# design.net
KiCad netlist of a schematic drawn in Altium Designer
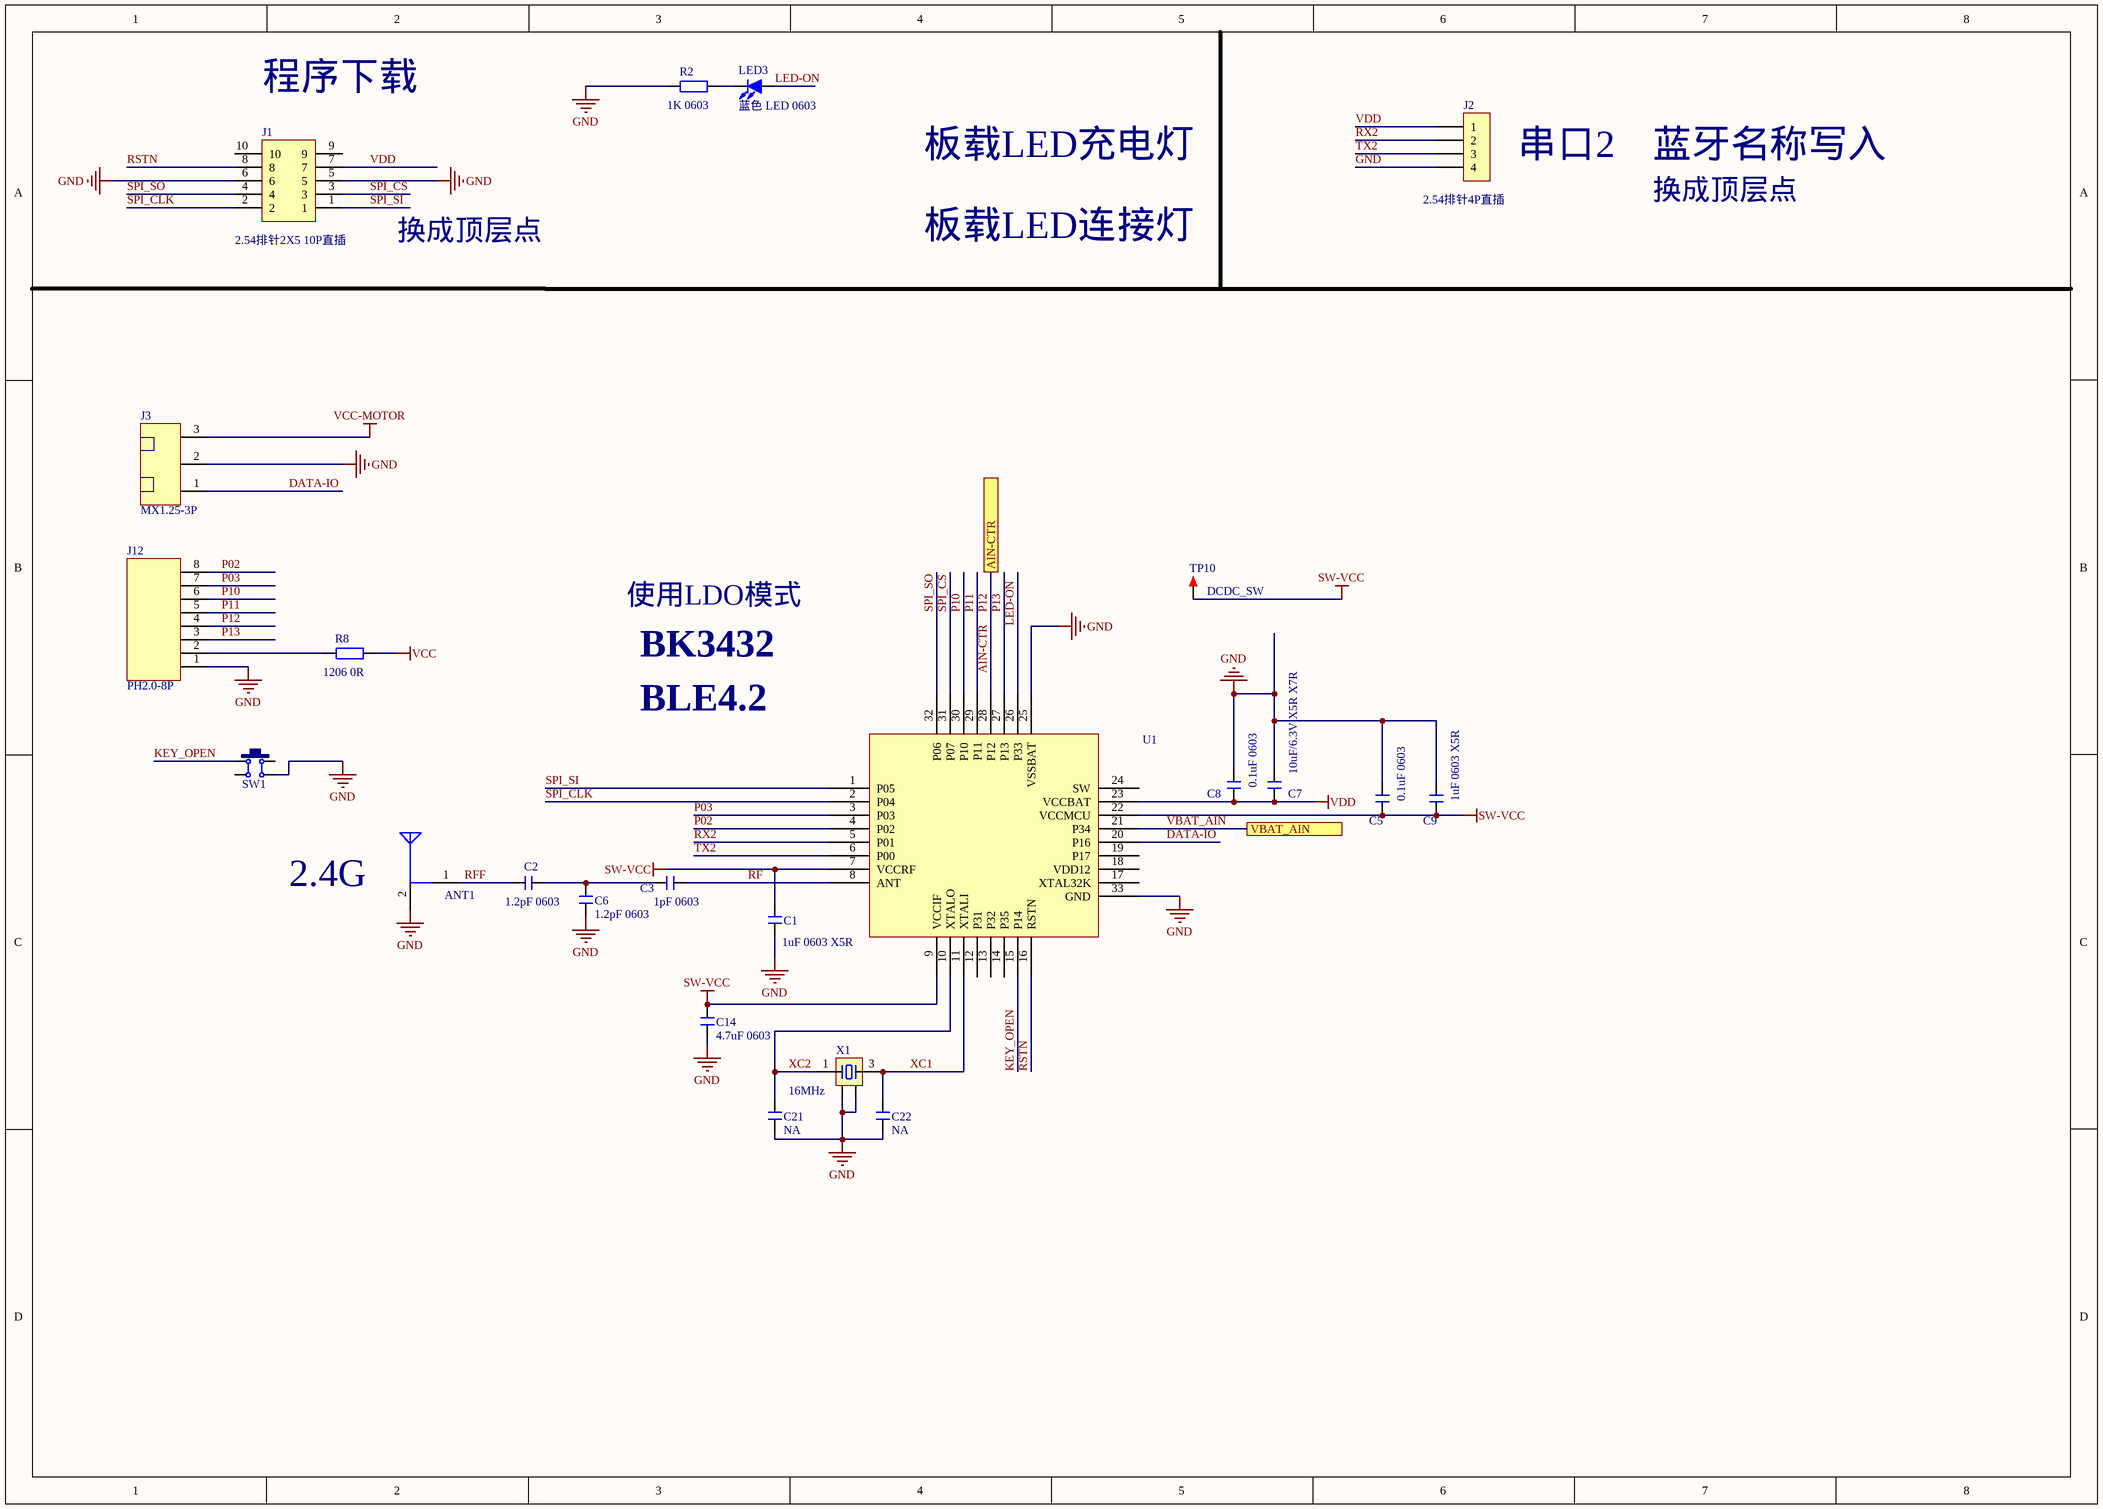
[diagram p0: 主控制器.SchDoc]

(export (version "E")
  (design (tool "Eeschema 10.0.6"))
  (components
    (comp (ref "ANT1")
      (value "Board_RF")
      (footprint "BK3432-RF-2")
      (description "SMA-板载2.4G射频天线")
      (fields (field (name "版权归属") "源创客"))
      (libsource (lib "this") (part "SMA-2"))
    )
    (comp (ref "C1")
      (value "1uF 0603 X5R")
      (footprint "C 0603")
      (description "无极性贴片电容")
      (fields (field (name "版权归属") "源创客"))
      (libsource (lib "源创客") (part "C"))
    )
    (comp (ref "C2")
      (value "1.2pF 0603")
      (footprint "C 0603")
      (description "无极性贴片电容")
      (fields (field (name "版权归属") "源创客"))
      (libsource (lib "源创客") (part "C"))
    )
    (comp (ref "C3")
      (value "1pF 0603")
      (footprint "C 0603")
      (description "无极性贴片电容")
      (fields (field (name "版权归属") "源创客"))
      (libsource (lib "源创客") (part "C"))
    )
    (comp (ref "C5")
      (value "0.1uF 0603")
      (footprint "C 0603")
      (description "无极性贴片电容")
      (fields (field (name "版权归属") "源创客"))
      (libsource (lib "源创客") (part "C"))
    )
    (comp (ref "C6")
      (value "1.2pF 0603")
      (footprint "C 0603")
      (description "无极性贴片电容")
      (fields (field (name "版权归属") "源创客"))
      (libsource (lib "源创客") (part "C"))
    )
    (comp (ref "C7")
      (value "10uF/6.3V X5R X7R")
      (footprint "C 0603")
      (description "无极性贴片电容")
      (fields (field (name "版权归属") "源创客"))
      (libsource (lib "源创客") (part "C"))
    )
    (comp (ref "C8")
      (value "0.1uF 0603")
      (footprint "C 0603")
      (description "无极性贴片电容")
      (fields (field (name "版权归属") "源创客"))
      (libsource (lib "源创客") (part "C"))
    )
    (comp (ref "C9")
      (value "1uF 0603 X5R")
      (footprint "C 0603")
      (description "无极性贴片电容")
      (fields (field (name "版权归属") "源创客"))
      (libsource (lib "源创客") (part "C"))
    )
    (comp (ref "C14")
      (value "4.7uF 0603")
      (footprint "C 0603")
      (description "无极性贴片电容")
      (fields (field (name "版权归属") "源创客"))
      (libsource (lib "源创客") (part "C"))
    )
    (comp (ref "C21")
      (value "NA")
      (footprint "C 0603")
      (description "无极性贴片电容")
      (fields (field (name "版权归属") "源创客"))
      (libsource (lib "源创客") (part "C"))
    )
    (comp (ref "C22")
      (value "NA")
      (footprint "C 0603")
      (description "无极性贴片电容")
      (fields (field (name "版权归属") "源创客"))
      (libsource (lib "源创客") (part "C"))
    )
    (comp (ref "J1")
      (value "2.54排针2X5 10P直插")
      (footprint "Pin HDR2X5/2.54mm")
      (libsource (lib "排针") (part "Pin HDR2X5"))
    )
    (comp (ref "J2")
      (value "2.54排针4P直插")
      (footprint "Pin HDR2.54MM/1X4")
      (libsource (lib "排针") (part "Pin HDR1X4"))
    )
    (comp (ref "J3") (value "MX1.25-3P") (footprint "MX1.25S-3P") (libsource (lib "MX") (part "MX1.25-3P")))
    (comp (ref "J12") (value "PH2.0-8P") (footprint "PH2.0-8P") (libsource (lib "PH") (part "PH2.0-8P")))
    (comp (ref "LED3")
      (value "蓝色 LED 0603")
      (footprint "LED 0603G")
      (description "贴片LED")
      (fields (field (name "版权归属") "源创客"))
      (libsource (lib "源创客") (part "LED-SMD"))
    )
    (comp (ref "R2")
      (value "1K 0603")
      (footprint "R 0603")
      (description "贴片电阻")
      (fields (field (name "版权归属") "源创客"))
      (libsource (lib "源创客") (part "R"))
    )
    (comp (ref "R8")
      (value "1206 0R")
      (footprint "R 1206")
      (description "贴片电阻")
      (fields (field (name "版权归属") "源创客"))
      (libsource (lib "源创客") (part "R"))
    )
    (comp (ref "SW1")
      (value "6x6x5")
      (footprint "TSW SMD-6*6*4.3")
      (description "贴片6x6轻触开关")
      (fields (field (name "版权归属") "源创客"))
      (libsource (lib "源创客") (part "TSW SMD-6x6"))
    )
    (comp (ref "TP10")
      (value "DCDC_SW")
      (footprint "TEST 1")
      (description "测试环")
      (fields (field (name "版权归属") "源创客"))
      (libsource (lib "源创客") (part "TEST TP"))
    )
    (comp (ref "U1")
      (value "BK3432 QFN32")
      (footprint "QFN32")
      (libsource (lib "this") (part "BK3432 QFN32"))
    )
    (comp (ref "X1")
      (value "16MHz")
      (footprint "OSC 3225-4P")
      (description "4脚无源晶振")
      (libsource (lib "晶振") (part "XTAL-4P"))
    )
  )
  (nets
    (net (code "1") (name "/AIN-CTR") (class "Default")
      (node (ref "J12") (pin "4") (pinfunction "4_4") (pintype "passive"))
      (node (ref "U1") (pin "28") (pinfunction "P12_28") (pintype "passive"))
    )
    (net (code "2") (name "/DATA-IO") (class "Default")
      (node (ref "J3") (pin "1") (pinfunction "1_1") (pintype "passive"))
      (node (ref "U1") (pin "20") (pinfunction "P16_20") (pintype "passive"))
    )
    (net (code "3") (name "/KEY_OPEN") (class "Default")
      (node (ref "SW1") (pin "1") (pinfunction "1_1") (pintype "passive"))
      (node (ref "U1") (pin "15") (pinfunction "P14_15") (pintype "passive"))
    )
    (net (code "4") (name "/LED-ON") (class "Default")
      (node (ref "LED3") (pin "1") (pinfunction "A_1") (pintype "passive"))
      (node (ref "U1") (pin "26") (pinfunction "P33_26") (pintype "passive"))
    )
    (net (code "5") (name "/P02") (class "Default")
      (node (ref "J12") (pin "8") (pinfunction "8_8") (pintype "passive"))
      (node (ref "U1") (pin "4") (pinfunction "P02_4") (pintype "passive"))
    )
    (net (code "6") (name "/P03") (class "Default")
      (node (ref "J12") (pin "7") (pinfunction "7_7") (pintype "passive"))
      (node (ref "U1") (pin "3") (pinfunction "P03_3") (pintype "passive"))
    )
    (net (code "7") (name "/P10") (class "Default")
      (node (ref "J12") (pin "6") (pinfunction "6_6") (pintype "passive"))
      (node (ref "U1") (pin "30") (pinfunction "P10_30") (pintype "passive"))
    )
    (net (code "8") (name "/P11") (class "Default")
      (node (ref "J12") (pin "5") (pinfunction "5_5") (pintype "passive"))
      (node (ref "U1") (pin "29") (pinfunction "P11_29") (pintype "passive"))
    )
    (net (code "9") (name "/P13") (class "Default")
      (node (ref "J12") (pin "3") (pinfunction "3_3") (pintype "passive"))
      (node (ref "U1") (pin "27") (pinfunction "P13_27") (pintype "passive"))
    )
    (net (code "10") (name "/RF") (class "Default")
      (node (ref "C3") (pin "2") (pinfunction "2_2") (pintype "passive"))
      (node (ref "U1") (pin "8") (pinfunction "ANT_8") (pintype "passive"))
    )
    (net (code "11") (name "/RFF") (class "Default")
      (node (ref "ANT1") (pin "1") (pinfunction "ANT_1") (pintype "passive"))
      (node (ref "C2") (pin "1") (pinfunction "1_1") (pintype "passive"))
    )
    (net (code "12") (name "/RSTN") (class "Default")
      (node (ref "J1") (pin "8") (pinfunction "8_8") (pintype "passive"))
      (node (ref "U1") (pin "16") (pinfunction "RSTN_16") (pintype "passive"))
    )
    (net (code "13") (name "/RX2") (class "Default")
      (node (ref "J2") (pin "2") (pinfunction "2_2") (pintype "passive"))
      (node (ref "U1") (pin "5") (pinfunction "P01_5") (pintype "passive"))
    )
    (net (code "14") (name "/SPI_CLK") (class "Default")
      (node (ref "J1") (pin "2") (pinfunction "2_2") (pintype "passive"))
      (node (ref "U1") (pin "2") (pinfunction "P04_2") (pintype "passive"))
    )
    (net (code "15") (name "/SPI_CS") (class "Default")
      (node (ref "J1") (pin "3") (pinfunction "3_3") (pintype "passive"))
      (node (ref "U1") (pin "31") (pinfunction "P07_31") (pintype "passive"))
    )
    (net (code "16") (name "/SPI_SI") (class "Default")
      (node (ref "J1") (pin "1") (pinfunction "1_1") (pintype "passive"))
      (node (ref "U1") (pin "1") (pinfunction "P05_1") (pintype "passive"))
    )
    (net (code "17") (name "/SPI_SO") (class "Default")
      (node (ref "J1") (pin "4") (pinfunction "4_4") (pintype "passive"))
      (node (ref "U1") (pin "32") (pinfunction "P06_32") (pintype "passive"))
    )
    (net (code "18") (name "/TX2") (class "Default")
      (node (ref "J2") (pin "3") (pinfunction "3_3") (pintype "passive"))
      (node (ref "U1") (pin "6") (pinfunction "P00_6") (pintype "passive"))
    )
    (net (code "19") (name "/VBAT_AIN") (class "Default")
      (node (ref "U1") (pin "21") (pinfunction "P34_21") (pintype "passive"))
    )
    (net (code "20") (name "/XC1") (class "Default")
      (node (ref "C22") (pin "2") (pinfunction "2_2") (pintype "passive"))
      (node (ref "U1") (pin "11") (pinfunction "XTALI_11") (pintype "passive"))
      (node (ref "X1") (pin "3") (pinfunction "3_3") (pintype "passive"))
    )
    (net (code "21") (name "/XC2") (class "Default")
      (node (ref "C21") (pin "2") (pinfunction "2_2") (pintype "passive"))
      (node (ref "U1") (pin "10") (pinfunction "XTALO_10") (pintype "passive"))
      (node (ref "X1") (pin "1") (pinfunction "1_1") (pintype "passive"))
    )
    (net (code "22") (name "GND") (class "Default")
      (node (ref "C1") (pin "1") (pinfunction "1_1") (pintype "passive"))
      (node (ref "C14") (pin "1") (pinfunction "1_1") (pintype "passive"))
      (node (ref "C21") (pin "1") (pinfunction "1_1") (pintype "passive"))
      (node (ref "C22") (pin "1") (pinfunction "1_1") (pintype "passive"))
      (node (ref "C5") (pin "1") (pinfunction "1_1") (pintype "passive"))
      (node (ref "C6") (pin "1") (pinfunction "1_1") (pintype "passive"))
      (node (ref "C7") (pin "1") (pinfunction "1_1") (pintype "passive"))
      (node (ref "C8") (pin "1") (pinfunction "1_1") (pintype "passive"))
      (node (ref "C9") (pin "1") (pinfunction "1_1") (pintype "passive"))
      (node (ref "J1") (pin "5") (pinfunction "5_5") (pintype "passive"))
      (node (ref "J1") (pin "6") (pinfunction "6_6") (pintype "passive"))
      (node (ref "J12") (pin "1") (pinfunction "1_1") (pintype "passive"))
      (node (ref "J2") (pin "4") (pinfunction "4_4") (pintype "passive"))
      (node (ref "J3") (pin "2") (pinfunction "2_2") (pintype "passive"))
      (node (ref "R2") (pin "1") (pinfunction "1_1") (pintype "passive"))
      (node (ref "SW1") (pin "3") (pinfunction "3_3") (pintype "passive"))
      (node (ref "U1") (pin "25") (pinfunction "VSSBAT_25") (pintype "passive"))
      (node (ref "U1") (pin "33") (pinfunction "GND_33") (pintype "passive"))
      (node (ref "X1") (pin "2") (pinfunction "2_2") (pintype "passive"))
      (node (ref "X1") (pin "4") (pinfunction "4_4") (pintype "passive"))
    )
    (net (code "23") (name "Net-(C2-Pad2)") (class "Default")
      (node (ref "C2") (pin "2") (pinfunction "2_2") (pintype "passive"))
      (node (ref "C3") (pin "1") (pinfunction "1_1") (pintype "passive"))
      (node (ref "C6") (pin "2") (pinfunction "2_2") (pintype "passive"))
    )
    (net (code "24") (name "Net-(J12-Pad2)") (class "Default")
      (node (ref "J12") (pin "2") (pinfunction "2_2") (pintype "passive"))
      (node (ref "R8") (pin "1") (pinfunction "1_1") (pintype "passive"))
    )
    (net (code "25") (name "Net-(LED3-K)") (class "Default")
      (node (ref "LED3") (pin "2") (pinfunction "K_2") (pintype "passive"))
      (node (ref "R2") (pin "2") (pinfunction "2_2") (pintype "passive"))
    )
    (net (code "26") (name "SW-VCC") (class "Default")
      (node (ref "C1") (pin "2") (pinfunction "2_2") (pintype "passive"))
      (node (ref "C14") (pin "2") (pinfunction "2_2") (pintype "passive"))
      (node (ref "C5") (pin "2") (pinfunction "2_2") (pintype "passive"))
      (node (ref "C9") (pin "2") (pinfunction "2_2") (pintype "passive"))
      (node (ref "TP10") (pin "1") (pinfunction "1_1") (pintype "passive"))
      (node (ref "U1") (pin "22") (pinfunction "VCCMCU_22") (pintype "passive"))
      (node (ref "U1") (pin "7") (pinfunction "VCCRF_7") (pintype "passive"))
      (node (ref "U1") (pin "9") (pinfunction "VCCIF_9") (pintype "passive"))
    )
    (net (code "27") (name "VCC") (class "Default")
      (node (ref "R8") (pin "2") (pinfunction "2_2") (pintype "passive"))
    )
    (net (code "28") (name "VCC-MOTOR") (class "Default")
      (node (ref "J3") (pin "3") (pinfunction "3_3") (pintype "passive"))
    )
    (net (code "29") (name "VDD") (class "Default")
      (node (ref "C7") (pin "2") (pinfunction "2_2") (pintype "passive"))
      (node (ref "C8") (pin "2") (pinfunction "2_2") (pintype "passive"))
      (node (ref "J1") (pin "7") (pinfunction "7_7") (pintype "passive"))
      (node (ref "J2") (pin "1") (pinfunction "1_1") (pintype "passive"))
      (node (ref "U1") (pin "23") (pinfunction "VCCBAT_23") (pintype "passive"))
    )
    (net (code "30") (name "unconnected-(ANT1-GND-Pad2)") (class "Default")
      (node (ref "ANT1") (pin "2") (pinfunction "GND_2") (pintype "passive"))
    )
    (net (code "31") (name "unconnected-(J1-Pad9)") (class "Default")
      (node (ref "J1") (pin "9") (pinfunction "9_9") (pintype "passive"))
    )
    (net (code "32") (name "unconnected-(J1-Pad10)") (class "Default")
      (node (ref "J1") (pin "10") (pinfunction "10_10") (pintype "passive"))
    )
    (net (code "33") (name "unconnected-(SW1-Pad2)") (class "Default")
      (node (ref "SW1") (pin "2") (pinfunction "2_2") (pintype "passive"))
    )
    (net (code "34") (name "unconnected-(SW1-Pad4)") (class "Default")
      (node (ref "SW1") (pin "4") (pinfunction "4_4") (pintype "passive"))
    )
    (net (code "35") (name "unconnected-(U1-P17-Pad19)") (class "Default")
      (node (ref "U1") (pin "19") (pinfunction "P17_19") (pintype "passive"))
    )
    (net (code "36") (name "unconnected-(U1-P31-Pad12)") (class "Default")
      (node (ref "U1") (pin "12") (pinfunction "P31_12") (pintype "passive"))
    )
    (net (code "37") (name "unconnected-(U1-P32-Pad13)") (class "Default")
      (node (ref "U1") (pin "13") (pinfunction "P32_13") (pintype "passive"))
    )
    (net (code "38") (name "unconnected-(U1-P35-Pad14)") (class "Default")
      (node (ref "U1") (pin "14") (pinfunction "P35_14") (pintype "passive"))
    )
    (net (code "39") (name "unconnected-(U1-SW-Pad24)") (class "Default")
      (node (ref "U1") (pin "24") (pinfunction "SW_24") (pintype "passive"))
    )
    (net (code "40") (name "unconnected-(U1-VDD12-Pad18)") (class "Default")
      (node (ref "U1") (pin "18") (pinfunction "VDD12_18") (pintype "passive"))
    )
    (net (code "41") (name "unconnected-(U1-XTAL32K-Pad17)") (class "Default")
      (node (ref "U1") (pin "17") (pinfunction "XTAL32K_17") (pintype "passive"))
    )
  )
)
